# Blinker_07.net
KiCad netlist of a schematic drawn in EAGLE
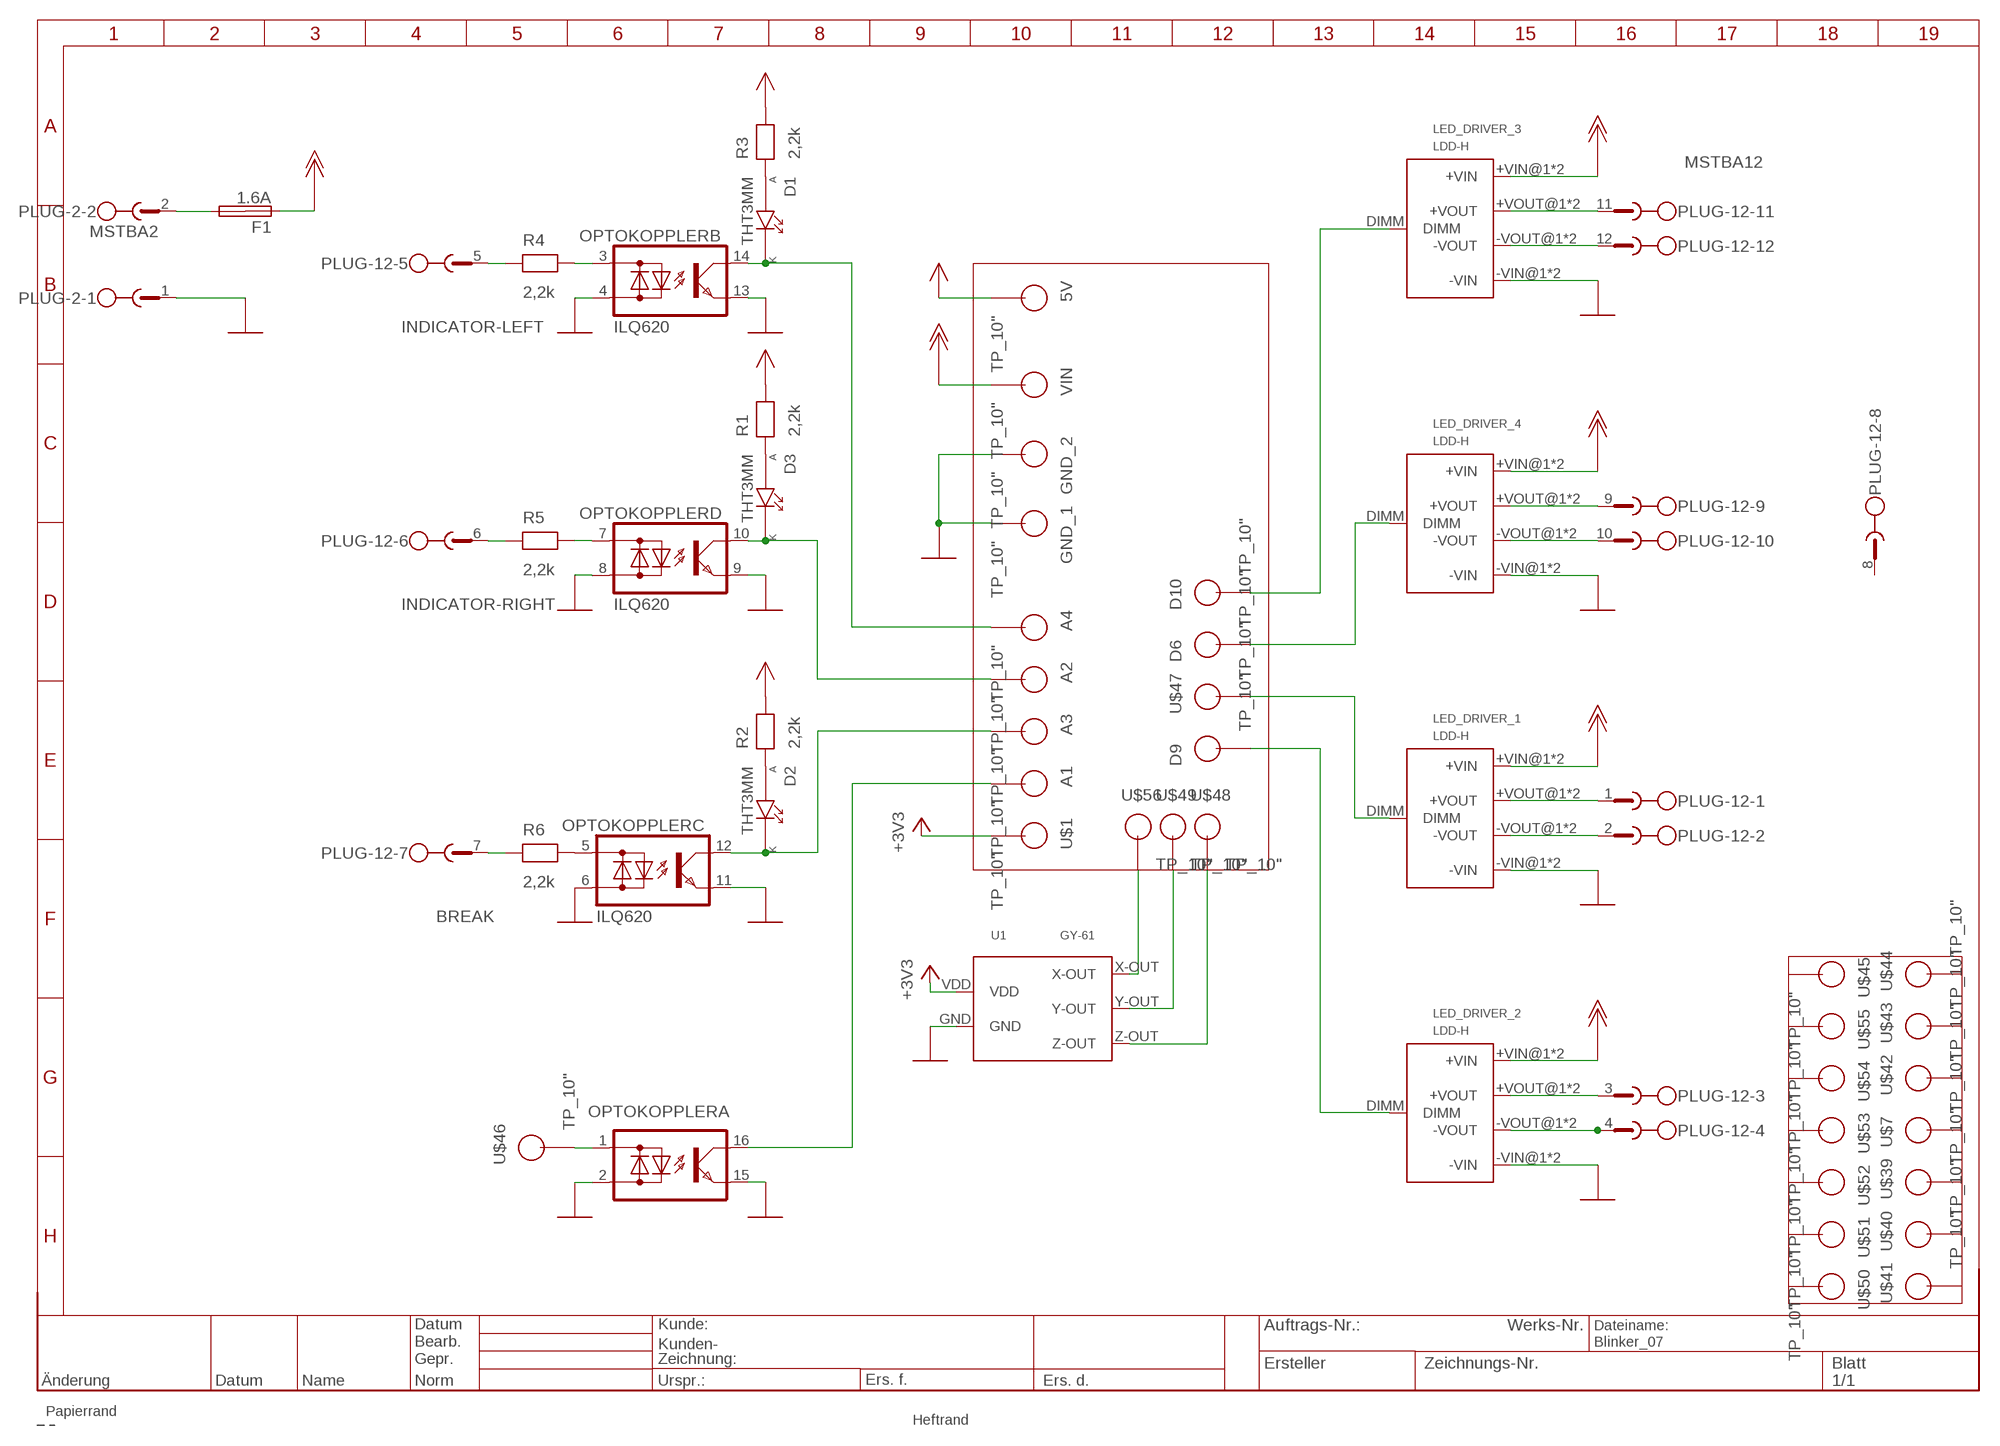
[diagram p0: schematic, sheet 1]

(export (version "E")
  (design (tool "Eeschema 10.0.6"))
  (components
    (comp (ref "5V")
      (value "TP_10\"")
      (footprint "eagle-import:TP_10")
      (libsource (lib "eagle-import") (part "TP_10{dblquote}"))
    )
    (comp (ref "A1")
      (value "TP_10\"")
      (footprint "eagle-import:TP_10")
      (libsource (lib "eagle-import") (part "TP_10{dblquote}"))
    )
    (comp (ref "A2")
      (value "TP_10\"")
      (footprint "eagle-import:TP_10")
      (libsource (lib "eagle-import") (part "TP_10{dblquote}"))
    )
    (comp (ref "A3")
      (value "TP_10\"")
      (footprint "eagle-import:TP_10")
      (libsource (lib "eagle-import") (part "TP_10{dblquote}"))
    )
    (comp (ref "A4")
      (value "TP_10\"")
      (footprint "eagle-import:TP_10")
      (libsource (lib "eagle-import") (part "TP_10{dblquote}"))
    )
    (comp (ref "D1")
      (value "THT3MM")
      (footprint "eagle-import:THT3MM")
      (libsource (lib "eagle-import") (part "THT3MM"))
    )
    (comp (ref "D2")
      (value "THT3MM")
      (footprint "eagle-import:THT3MM")
      (libsource (lib "eagle-import") (part "THT3MM"))
    )
    (comp (ref "D3")
      (value "THT3MM")
      (footprint "eagle-import:THT3MM")
      (libsource (lib "eagle-import") (part "THT3MM"))
    )
    (comp (ref "D6")
      (value "TP_10\"")
      (footprint "eagle-import:TP_10")
      (libsource (lib "eagle-import") (part "TP_10{dblquote}"))
    )
    (comp (ref "D9")
      (value "TP_10\"")
      (footprint "eagle-import:TP_10")
      (libsource (lib "eagle-import") (part "TP_10{dblquote}"))
    )
    (comp (ref "D10")
      (value "TP_10\"")
      (footprint "eagle-import:TP_10")
      (libsource (lib "eagle-import") (part "TP_10{dblquote}"))
    )
    (comp (ref "F1")
      (value "1.6A")
      (footprint "eagle-import:SHK20Q")
      (libsource (lib "eagle-import") (part "SHK20Q"))
    )
    (comp (ref "GND_1")
      (value "TP_10\"")
      (footprint "eagle-import:TP_10")
      (libsource (lib "eagle-import") (part "TP_10{dblquote}"))
    )
    (comp (ref "GND_2")
      (value "TP_10\"")
      (footprint "eagle-import:TP_10")
      (libsource (lib "eagle-import") (part "TP_10{dblquote}"))
    )
    (comp (ref "LED_DRIVER_1")
      (value "LDD-H")
      (footprint "eagle-import:LDD-H")
      (libsource (lib "eagle-import") (part "LDD-H"))
    )
    (comp (ref "LED_DRIVER_2")
      (value "LDD-H")
      (footprint "eagle-import:LDD-H")
      (libsource (lib "eagle-import") (part "LDD-H"))
    )
    (comp (ref "LED_DRIVER_3")
      (value "LDD-H")
      (footprint "eagle-import:LDD-H")
      (libsource (lib "eagle-import") (part "LDD-H"))
    )
    (comp (ref "LED_DRIVER_4")
      (value "LDD-H")
      (footprint "eagle-import:LDD-H")
      (libsource (lib "eagle-import") (part "LDD-H"))
    )
    (comp (ref "OPTOKOPPLER")
      (value "ILQ620")
      (footprint "eagle-import:DIL16")
      (libsource (lib "eagle-import") (part "ILQ620"))
    )
    (comp (ref "PLUG-2")
      (value "MSTBA2")
      (footprint "eagle-import:MSTBA2")
      (fields (field (name "MF") "FARNELL") (field (name "MPN") "1757242"))
      (libsource (lib "eagle-import") (part "MSTBA2"))
    )
    (comp (ref "PLUG-12")
      (value "MSTBA12")
      (footprint "eagle-import:MSTBA12")
      (fields (field (name "MPN") "1757349"))
      (libsource (lib "eagle-import") (part "MSTBA12"))
    )
    (comp (ref "R1")
      (value "2,2k")
      (footprint "eagle-import:R-10")
      (libsource (lib "eagle-import") (part "RESEU-10"))
    )
    (comp (ref "R2")
      (value "2,2k")
      (footprint "eagle-import:R-10")
      (libsource (lib "eagle-import") (part "RESEU-10"))
    )
    (comp (ref "R3")
      (value "2,2k")
      (footprint "eagle-import:R-10")
      (libsource (lib "eagle-import") (part "RESEU-10"))
    )
    (comp (ref "R4")
      (value "2,2k")
      (footprint "eagle-import:R-10")
      (libsource (lib "eagle-import") (part "RESEU-10"))
    )
    (comp (ref "R5")
      (value "2,2k")
      (footprint "eagle-import:R-10")
      (libsource (lib "eagle-import") (part "RESEU-10"))
    )
    (comp (ref "R6")
      (value "2,2k")
      (footprint "eagle-import:R-10")
      (libsource (lib "eagle-import") (part "RESEU-10"))
    )
    (comp (ref "U$1")
      (value "TP_10\"")
      (footprint "eagle-import:TP_10")
      (libsource (lib "eagle-import") (part "TP_10{dblquote}"))
    )
    (comp (ref "U$7")
      (value "TP_10\"")
      (footprint "eagle-import:TP_10")
      (libsource (lib "eagle-import") (part "TP_10{dblquote}"))
    )
    (comp (ref "U$39")
      (value "TP_10\"")
      (footprint "eagle-import:TP_10")
      (libsource (lib "eagle-import") (part "TP_10{dblquote}"))
    )
    (comp (ref "U$40")
      (value "TP_10\"")
      (footprint "eagle-import:TP_10")
      (libsource (lib "eagle-import") (part "TP_10{dblquote}"))
    )
    (comp (ref "U$41")
      (value "TP_10\"")
      (footprint "eagle-import:TP_10")
      (libsource (lib "eagle-import") (part "TP_10{dblquote}"))
    )
    (comp (ref "U$42")
      (value "TP_10\"")
      (footprint "eagle-import:TP_10")
      (libsource (lib "eagle-import") (part "TP_10{dblquote}"))
    )
    (comp (ref "U$43")
      (value "TP_10\"")
      (footprint "eagle-import:TP_10")
      (libsource (lib "eagle-import") (part "TP_10{dblquote}"))
    )
    (comp (ref "U$44")
      (value "TP_10\"")
      (footprint "eagle-import:TP_10")
      (libsource (lib "eagle-import") (part "TP_10{dblquote}"))
    )
    (comp (ref "U$45")
      (value "TP_10\"")
      (footprint "eagle-import:TP_10")
      (libsource (lib "eagle-import") (part "TP_10{dblquote}"))
    )
    (comp (ref "U$46")
      (value "TP_10\"")
      (footprint "eagle-import:TP_10")
      (libsource (lib "eagle-import") (part "TP_10{dblquote}"))
    )
    (comp (ref "U$47")
      (value "TP_10\"")
      (footprint "eagle-import:TP_10")
      (libsource (lib "eagle-import") (part "TP_10{dblquote}"))
    )
    (comp (ref "U$48")
      (value "TP_10\"")
      (footprint "eagle-import:TP_10")
      (libsource (lib "eagle-import") (part "TP_10{dblquote}"))
    )
    (comp (ref "U$49")
      (value "TP_10\"")
      (footprint "eagle-import:TP_10")
      (libsource (lib "eagle-import") (part "TP_10{dblquote}"))
    )
    (comp (ref "U$50")
      (value "TP_10\"")
      (footprint "eagle-import:TP_10")
      (libsource (lib "eagle-import") (part "TP_10{dblquote}"))
    )
    (comp (ref "U$51")
      (value "TP_10\"")
      (footprint "eagle-import:TP_10")
      (libsource (lib "eagle-import") (part "TP_10{dblquote}"))
    )
    (comp (ref "U$52")
      (value "TP_10\"")
      (footprint "eagle-import:TP_10")
      (libsource (lib "eagle-import") (part "TP_10{dblquote}"))
    )
    (comp (ref "U$53")
      (value "TP_10\"")
      (footprint "eagle-import:TP_10")
      (libsource (lib "eagle-import") (part "TP_10{dblquote}"))
    )
    (comp (ref "U$54")
      (value "TP_10\"")
      (footprint "eagle-import:TP_10")
      (libsource (lib "eagle-import") (part "TP_10{dblquote}"))
    )
    (comp (ref "U$55")
      (value "TP_10\"")
      (footprint "eagle-import:TP_10")
      (libsource (lib "eagle-import") (part "TP_10{dblquote}"))
    )
    (comp (ref "U$56")
      (value "TP_10\"")
      (footprint "eagle-import:TP_10")
      (libsource (lib "eagle-import") (part "TP_10{dblquote}"))
    )
    (comp (ref "U1")
      (value "GY-61")
      (footprint "eagle-import:GY-61")
      (libsource (lib "eagle-import") (part "GY-61"))
    )
    (comp (ref "VIN")
      (value "TP_10\"")
      (footprint "eagle-import:TP_10")
      (libsource (lib "eagle-import") (part "TP_10{dblquote}"))
    )
  )
  (nets
    (net (code "1") (name "+3V3") (class "Default")
      (node (ref "U$1") (pin "P$1") (pinfunction "TP_13_P$1") (pintype "bidirectional"))
      (node (ref "U1") (pin "VDD") (pinfunction "VDD_VDD") (pintype "power_in"))
    )
    (net (code "2") (name "+5V") (class "Default")
      (node (ref "5V") (pin "P$1") (pinfunction "TP_13_P$1") (pintype "bidirectional"))
      (node (ref "R1") (pin "2") (pinfunction "2_2") (pintype "passive"))
      (node (ref "R2") (pin "2") (pinfunction "2_2") (pintype "passive"))
      (node (ref "R3") (pin "2") (pinfunction "2_2") (pintype "passive"))
    )
    (net (code "3") (name "+12V") (class "Default")
      (node (ref "F1") (pin "1A") (pinfunction "1A_1A") (pintype "passive"))
      (node (ref "LED_DRIVER_1") (pin "+VIN@1") (pinfunction "+VIN_+VIN@1") (pintype "power_in"))
      (node (ref "LED_DRIVER_1") (pin "+VIN@2") (pinfunction "+VIN_+VIN@2") (pintype "power_in"))
      (node (ref "LED_DRIVER_2") (pin "+VIN@1") (pinfunction "+VIN_+VIN@1") (pintype "power_in"))
      (node (ref "LED_DRIVER_2") (pin "+VIN@2") (pinfunction "+VIN_+VIN@2") (pintype "power_in"))
      (node (ref "LED_DRIVER_3") (pin "+VIN@1") (pinfunction "+VIN_+VIN@1") (pintype "power_in"))
      (node (ref "LED_DRIVER_3") (pin "+VIN@2") (pinfunction "+VIN_+VIN@2") (pintype "power_in"))
      (node (ref "LED_DRIVER_4") (pin "+VIN@1") (pinfunction "+VIN_+VIN@1") (pintype "power_in"))
      (node (ref "LED_DRIVER_4") (pin "+VIN@2") (pinfunction "+VIN_+VIN@2") (pintype "power_in"))
      (node (ref "VIN") (pin "P$1") (pinfunction "TP_13_P$1") (pintype "bidirectional"))
    )
    (net (code "4") (name "/BREAK") (class "Default")
      (node (ref "PLUG-12") (pin "7") (pinfunction "1_7") (pintype "passive"))
      (node (ref "R6") (pin "1") (pinfunction "1_1") (pintype "passive"))
    )
    (net (code "5") (name "/INDICATOR-LEFT") (class "Default")
      (node (ref "PLUG-12") (pin "5") (pinfunction "1_5") (pintype "passive"))
      (node (ref "R4") (pin "1") (pinfunction "1_1") (pintype "passive"))
    )
    (net (code "6") (name "/INDICATOR-RIGHT") (class "Default")
      (node (ref "PLUG-12") (pin "6") (pinfunction "1_6") (pintype "passive"))
      (node (ref "R5") (pin "1") (pinfunction "1_1") (pintype "passive"))
    )
    (net (code "7") (name "GND") (class "Default")
      (node (ref "GND_1") (pin "P$1") (pinfunction "TP_13_P$1") (pintype "bidirectional"))
      (node (ref "GND_2") (pin "P$1") (pinfunction "TP_13_P$1") (pintype "bidirectional"))
      (node (ref "LED_DRIVER_1") (pin "-VIN@1") (pinfunction "-VIN_-VIN@1") (pintype "power_in"))
      (node (ref "LED_DRIVER_1") (pin "-VIN@2") (pinfunction "-VIN_-VIN@2") (pintype "power_in"))
      (node (ref "LED_DRIVER_2") (pin "-VIN@1") (pinfunction "-VIN_-VIN@1") (pintype "power_in"))
      (node (ref "LED_DRIVER_2") (pin "-VIN@2") (pinfunction "-VIN_-VIN@2") (pintype "power_in"))
      (node (ref "LED_DRIVER_3") (pin "-VIN@1") (pinfunction "-VIN_-VIN@1") (pintype "power_in"))
      (node (ref "LED_DRIVER_3") (pin "-VIN@2") (pinfunction "-VIN_-VIN@2") (pintype "power_in"))
      (node (ref "LED_DRIVER_4") (pin "-VIN@1") (pinfunction "-VIN_-VIN@1") (pintype "power_in"))
      (node (ref "LED_DRIVER_4") (pin "-VIN@2") (pinfunction "-VIN_-VIN@2") (pintype "power_in"))
      (node (ref "OPTOKOPPLER") (pin "11") (pinfunction "E_11") (pintype "passive"))
      (node (ref "OPTOKOPPLER") (pin "13") (pinfunction "E_13") (pintype "passive"))
      (node (ref "OPTOKOPPLER") (pin "15") (pinfunction "E_15") (pintype "passive"))
      (node (ref "OPTOKOPPLER") (pin "2") (pinfunction "AC2_2") (pintype "passive"))
      (node (ref "OPTOKOPPLER") (pin "4") (pinfunction "AC2_4") (pintype "passive"))
      (node (ref "OPTOKOPPLER") (pin "6") (pinfunction "AC2_6") (pintype "passive"))
      (node (ref "OPTOKOPPLER") (pin "8") (pinfunction "AC2_8") (pintype "passive"))
      (node (ref "OPTOKOPPLER") (pin "9") (pinfunction "E_9") (pintype "passive"))
      (node (ref "PLUG-2") (pin "1") (pinfunction "1_1") (pintype "passive"))
      (node (ref "U1") (pin "GND") (pinfunction "GND_GND") (pintype "power_in"))
    )
    (net (code "8") (name "Net-(A1-TP_13)") (class "Default")
      (node (ref "A1") (pin "P$1") (pinfunction "TP_13_P$1") (pintype "bidirectional"))
      (node (ref "OPTOKOPPLER") (pin "16") (pinfunction "C_16") (pintype "passive"))
    )
    (net (code "9") (name "Net-(A2-TP_13)") (class "Default")
      (node (ref "A2") (pin "P$1") (pinfunction "TP_13_P$1") (pintype "bidirectional"))
      (node (ref "D3") (pin "K") (pinfunction "P2K_K") (pintype "bidirectional"))
      (node (ref "OPTOKOPPLER") (pin "10") (pinfunction "C_10") (pintype "passive"))
    )
    (net (code "10") (name "Net-(A3-TP_13)") (class "Default")
      (node (ref "A3") (pin "P$1") (pinfunction "TP_13_P$1") (pintype "bidirectional"))
      (node (ref "D2") (pin "K") (pinfunction "P2K_K") (pintype "bidirectional"))
      (node (ref "OPTOKOPPLER") (pin "12") (pinfunction "C_12") (pintype "passive"))
    )
    (net (code "11") (name "Net-(A4-TP_13)") (class "Default")
      (node (ref "A4") (pin "P$1") (pinfunction "TP_13_P$1") (pintype "bidirectional"))
      (node (ref "D1") (pin "K") (pinfunction "P2K_K") (pintype "bidirectional"))
      (node (ref "OPTOKOPPLER") (pin "14") (pinfunction "C_14") (pintype "passive"))
    )
    (net (code "12") (name "Net-(D1-P1A)") (class "Default")
      (node (ref "D1") (pin "A") (pinfunction "P1A_A") (pintype "bidirectional"))
      (node (ref "R3") (pin "1") (pinfunction "1_1") (pintype "passive"))
    )
    (net (code "13") (name "Net-(D2-P1A)") (class "Default")
      (node (ref "D2") (pin "A") (pinfunction "P1A_A") (pintype "bidirectional"))
      (node (ref "R2") (pin "1") (pinfunction "1_1") (pintype "passive"))
    )
    (net (code "14") (name "Net-(D3-P1A)") (class "Default")
      (node (ref "D3") (pin "A") (pinfunction "P1A_A") (pintype "bidirectional"))
      (node (ref "R1") (pin "1") (pinfunction "1_1") (pintype "passive"))
    )
    (net (code "15") (name "Net-(D6-TP_13)") (class "Default")
      (node (ref "D6") (pin "P$1") (pinfunction "TP_13_P$1") (pintype "bidirectional"))
      (node (ref "LED_DRIVER_4") (pin "DIMM") (pinfunction "DIMM_DIMM") (pintype "input"))
    )
    (net (code "16") (name "Net-(D9-TP_13)") (class "Default")
      (node (ref "D9") (pin "P$1") (pinfunction "TP_13_P$1") (pintype "bidirectional"))
      (node (ref "LED_DRIVER_2") (pin "DIMM") (pinfunction "DIMM_DIMM") (pintype "input"))
    )
    (net (code "17") (name "Net-(D10-TP_13)") (class "Default")
      (node (ref "D10") (pin "P$1") (pinfunction "TP_13_P$1") (pintype "bidirectional"))
      (node (ref "LED_DRIVER_3") (pin "DIMM") (pinfunction "DIMM_DIMM") (pintype "input"))
    )
    (net (code "18") (name "Net-(LED_DRIVER_1-+VOUT-Pad+VOUT@1)") (class "Default")
      (node (ref "LED_DRIVER_1") (pin "+VOUT@1") (pinfunction "+VOUT_+VOUT@1") (pintype "output"))
      (node (ref "LED_DRIVER_1") (pin "+VOUT@2") (pinfunction "+VOUT_+VOUT@2") (pintype "output"))
      (node (ref "PLUG-12") (pin "1") (pinfunction "1_1") (pintype "passive"))
    )
    (net (code "19") (name "Net-(OPTOKOPPLERA-AC1)") (class "Default")
      (node (ref "OPTOKOPPLER") (pin "1") (pinfunction "AC1_1") (pintype "passive"))
      (node (ref "U$46") (pin "P$1") (pinfunction "TP_13_P$1") (pintype "bidirectional"))
    )
    (net (code "20") (name "Net-(OPTOKOPPLERB-AC1)") (class "Default")
      (node (ref "OPTOKOPPLER") (pin "3") (pinfunction "AC1_3") (pintype "passive"))
      (node (ref "R4") (pin "2") (pinfunction "2_2") (pintype "passive"))
    )
    (net (code "21") (name "Net-(OPTOKOPPLERC-AC1)") (class "Default")
      (node (ref "OPTOKOPPLER") (pin "5") (pinfunction "AC1_5") (pintype "passive"))
      (node (ref "R6") (pin "2") (pinfunction "2_2") (pintype "passive"))
    )
    (net (code "22") (name "Net-(OPTOKOPPLERD-AC1)") (class "Default")
      (node (ref "OPTOKOPPLER") (pin "7") (pinfunction "AC1_7") (pintype "passive"))
      (node (ref "R5") (pin "2") (pinfunction "2_2") (pintype "passive"))
    )
    (net (code "23") (name "Net-(PLUG-2B-1)") (class "Default")
      (node (ref "F1") (pin "2A") (pinfunction "2A_2A") (pintype "passive"))
      (node (ref "PLUG-2") (pin "2") (pinfunction "1_2") (pintype "passive"))
    )
    (net (code "24") (name "Net-(PLUG-12B-1)") (class "Default")
      (node (ref "LED_DRIVER_4") (pin "-VOUT@1") (pinfunction "-VOUT_-VOUT@1") (pintype "output"))
      (node (ref "LED_DRIVER_4") (pin "-VOUT@2") (pinfunction "-VOUT_-VOUT@2") (pintype "output"))
      (node (ref "PLUG-12") (pin "10") (pinfunction "1_10") (pintype "passive"))
    )
    (net (code "25") (name "Net-(PLUG-12C-1)") (class "Default")
      (node (ref "LED_DRIVER_3") (pin "+VOUT@1") (pinfunction "+VOUT_+VOUT@1") (pintype "output"))
      (node (ref "LED_DRIVER_3") (pin "+VOUT@2") (pinfunction "+VOUT_+VOUT@2") (pintype "output"))
      (node (ref "PLUG-12") (pin "11") (pinfunction "1_11") (pintype "passive"))
    )
    (net (code "26") (name "Net-(PLUG-12D-1)") (class "Default")
      (node (ref "LED_DRIVER_3") (pin "-VOUT@1") (pinfunction "-VOUT_-VOUT@1") (pintype "output"))
      (node (ref "LED_DRIVER_3") (pin "-VOUT@2") (pinfunction "-VOUT_-VOUT@2") (pintype "output"))
      (node (ref "PLUG-12") (pin "12") (pinfunction "1_12") (pintype "passive"))
    )
    (net (code "27") (name "Net-(PLUG-12E-1)") (class "Default")
      (node (ref "LED_DRIVER_1") (pin "-VOUT@1") (pinfunction "-VOUT_-VOUT@1") (pintype "output"))
      (node (ref "LED_DRIVER_1") (pin "-VOUT@2") (pinfunction "-VOUT_-VOUT@2") (pintype "output"))
      (node (ref "PLUG-12") (pin "2") (pinfunction "1_2") (pintype "passive"))
    )
    (net (code "28") (name "Net-(PLUG-12F-1)") (class "Default")
      (node (ref "LED_DRIVER_2") (pin "+VOUT@1") (pinfunction "+VOUT_+VOUT@1") (pintype "output"))
      (node (ref "LED_DRIVER_2") (pin "+VOUT@2") (pinfunction "+VOUT_+VOUT@2") (pintype "output"))
      (node (ref "PLUG-12") (pin "3") (pinfunction "1_3") (pintype "passive"))
    )
    (net (code "29") (name "Net-(PLUG-12G-1)") (class "Default")
      (node (ref "LED_DRIVER_2") (pin "-VOUT@1") (pinfunction "-VOUT_-VOUT@1") (pintype "output"))
      (node (ref "LED_DRIVER_2") (pin "-VOUT@2") (pinfunction "-VOUT_-VOUT@2") (pintype "output"))
      (node (ref "PLUG-12") (pin "4") (pinfunction "1_4") (pintype "passive"))
    )
    (net (code "30") (name "Net-(PLUG-12L-1)") (class "Default")
      (node (ref "LED_DRIVER_4") (pin "+VOUT@1") (pinfunction "+VOUT_+VOUT@1") (pintype "output"))
      (node (ref "LED_DRIVER_4") (pin "+VOUT@2") (pinfunction "+VOUT_+VOUT@2") (pintype "output"))
      (node (ref "PLUG-12") (pin "9") (pinfunction "1_9") (pintype "passive"))
    )
    (net (code "31") (name "Net-(U$47-TP_13)") (class "Default")
      (node (ref "LED_DRIVER_1") (pin "DIMM") (pinfunction "DIMM_DIMM") (pintype "input"))
      (node (ref "U$47") (pin "P$1") (pinfunction "TP_13_P$1") (pintype "bidirectional"))
    )
    (net (code "32") (name "Net-(U$48-TP_13)") (class "Default")
      (node (ref "U$48") (pin "P$1") (pinfunction "TP_13_P$1") (pintype "bidirectional"))
      (node (ref "U1") (pin "Z-OUT") (pinfunction "Z-OUT_Z-OUT") (pintype "output"))
    )
    (net (code "33") (name "Net-(U$49-TP_13)") (class "Default")
      (node (ref "U$49") (pin "P$1") (pinfunction "TP_13_P$1") (pintype "bidirectional"))
      (node (ref "U1") (pin "Y-OUT") (pinfunction "Y-OUT_Y-OUT") (pintype "output"))
    )
    (net (code "34") (name "Net-(U$56-TP_13)") (class "Default")
      (node (ref "U$56") (pin "P$1") (pinfunction "TP_13_P$1") (pintype "bidirectional"))
      (node (ref "U1") (pin "X-OUT") (pinfunction "X-OUT_X-OUT") (pintype "output"))
    )
    (net (code "35") (name "unconnected-(F1-Pad1B)") (class "Default")
      (node (ref "F1") (pin "1B") (pinfunction "1B_1B") (pintype "passive"))
    )
    (net (code "36") (name "unconnected-(F1-Pad2B)") (class "Default")
      (node (ref "F1") (pin "2B") (pinfunction "2B_2B") (pintype "passive"))
    )
    (net (code "37") (name "unconnected-(PLUG-12K-1-Pad8)") (class "Default")
      (node (ref "PLUG-12") (pin "8") (pinfunction "1_8") (pintype "passive"))
    )
    (net (code "38") (name "unconnected-(U$7-TP_13-PadP$1)") (class "Default")
      (node (ref "U$7") (pin "P$1") (pinfunction "TP_13_P$1") (pintype "bidirectional"))
    )
    (net (code "39") (name "unconnected-(U$39-TP_13-PadP$1)") (class "Default")
      (node (ref "U$39") (pin "P$1") (pinfunction "TP_13_P$1") (pintype "bidirectional"))
    )
    (net (code "40") (name "unconnected-(U$40-TP_13-PadP$1)") (class "Default")
      (node (ref "U$40") (pin "P$1") (pinfunction "TP_13_P$1") (pintype "bidirectional"))
    )
    (net (code "41") (name "unconnected-(U$41-TP_13-PadP$1)") (class "Default")
      (node (ref "U$41") (pin "P$1") (pinfunction "TP_13_P$1") (pintype "bidirectional"))
    )
    (net (code "42") (name "unconnected-(U$42-TP_13-PadP$1)") (class "Default")
      (node (ref "U$42") (pin "P$1") (pinfunction "TP_13_P$1") (pintype "bidirectional"))
    )
    (net (code "43") (name "unconnected-(U$43-TP_13-PadP$1)") (class "Default")
      (node (ref "U$43") (pin "P$1") (pinfunction "TP_13_P$1") (pintype "bidirectional"))
    )
    (net (code "44") (name "unconnected-(U$44-TP_13-PadP$1)") (class "Default")
      (node (ref "U$44") (pin "P$1") (pinfunction "TP_13_P$1") (pintype "bidirectional"))
    )
    (net (code "45") (name "unconnected-(U$45-TP_13-PadP$1)") (class "Default")
      (node (ref "U$45") (pin "P$1") (pinfunction "TP_13_P$1") (pintype "bidirectional"))
    )
    (net (code "46") (name "unconnected-(U$50-TP_13-PadP$1)") (class "Default")
      (node (ref "U$50") (pin "P$1") (pinfunction "TP_13_P$1") (pintype "bidirectional"))
    )
    (net (code "47") (name "unconnected-(U$51-TP_13-PadP$1)") (class "Default")
      (node (ref "U$51") (pin "P$1") (pinfunction "TP_13_P$1") (pintype "bidirectional"))
    )
    (net (code "48") (name "unconnected-(U$52-TP_13-PadP$1)") (class "Default")
      (node (ref "U$52") (pin "P$1") (pinfunction "TP_13_P$1") (pintype "bidirectional"))
    )
    (net (code "49") (name "unconnected-(U$53-TP_13-PadP$1)") (class "Default")
      (node (ref "U$53") (pin "P$1") (pinfunction "TP_13_P$1") (pintype "bidirectional"))
    )
    (net (code "50") (name "unconnected-(U$54-TP_13-PadP$1)") (class "Default")
      (node (ref "U$54") (pin "P$1") (pinfunction "TP_13_P$1") (pintype "bidirectional"))
    )
    (net (code "51") (name "unconnected-(U$55-TP_13-PadP$1)") (class "Default")
      (node (ref "U$55") (pin "P$1") (pinfunction "TP_13_P$1") (pintype "bidirectional"))
    )
  )
)
